# F4AIR_-.net
KiCad netlist of a schematic drawn in Altium Designer
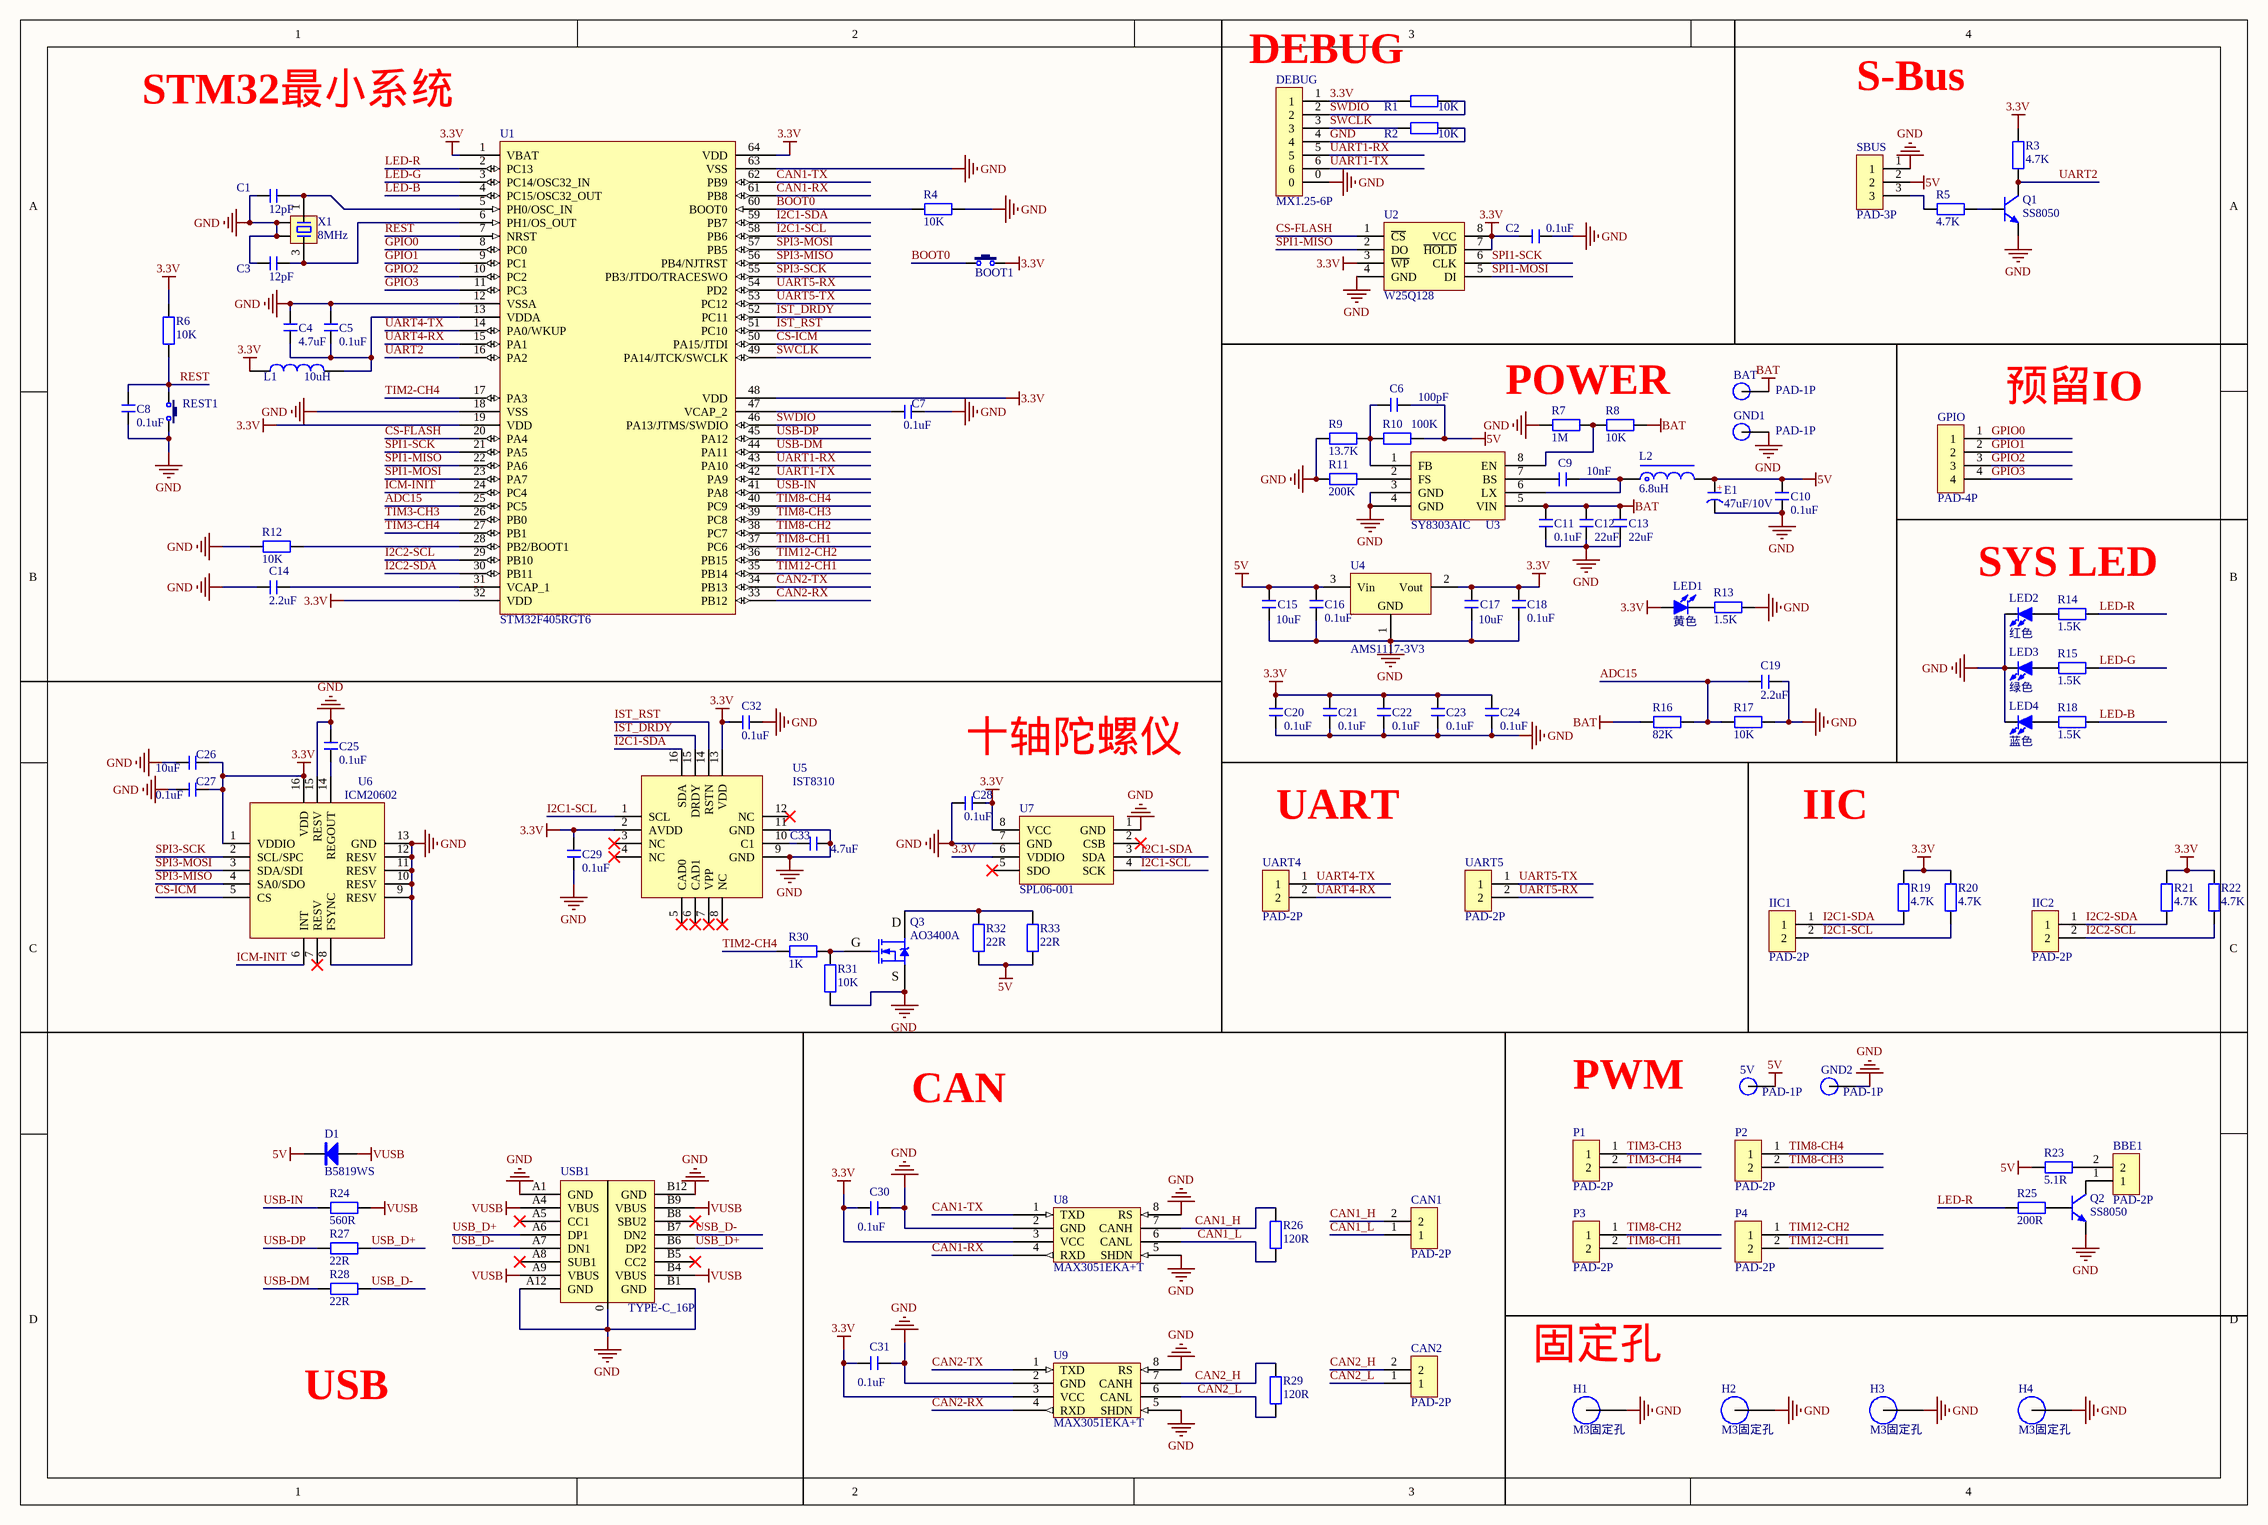
[diagram p0: F4AIR - 副本.SchDoc]

(export (version "E")
  (design (tool "Eeschema 10.0.6"))
  (components
    (comp (ref "5V") (value "PAD-1P") (footprint "PAD-4x2mm") (libsource (lib "F4AIR") (part "PAD-1P")))
    (comp (ref "BAT") (value "PAD-1P") (footprint "PAD-4x2mm") (libsource (lib "F4AIR") (part "PAD-1P")))
    (comp (ref "BBE1") (value "PAD-2P") (footprint "PAD-2.54-2P") (libsource (lib "") (part "PAD-2P_1")))
    (comp (ref "BOOT1")
      (value "3x6x5")
      (footprint "TSW SMD-3*6*5")
      (description "3x6轻触开关")
      (fields (field (name "版权归属") "源创客"))
      (libsource (lib "Schlib1") (part "TSW 3x6"))
    )
    (comp (ref "C1")
      (value "12pF")
      (footprint "C 0603_M")
      (description "无极性贴片电容")
      (fields (field (name "版权归属") "源创客"))
      (libsource (lib "Schlib1") (part "C"))
    )
    (comp (ref "C2")
      (value "0.1uF")
      (footprint "C 0603_M")
      (description "无极性贴片电容")
      (fields (field (name "版权归属") "源创客"))
      (libsource (lib "Schlib") (part "C"))
    )
    (comp (ref "C3")
      (value "12pF")
      (footprint "C 0603_M")
      (description "无极性贴片电容")
      (fields (field (name "版权归属") "源创客"))
      (libsource (lib "Schlib1") (part "C"))
    )
    (comp (ref "C4")
      (value "4.7uF")
      (footprint "C 0603_M")
      (description "无极性贴片电容")
      (fields (field (name "版权归属") "源创客"))
      (libsource (lib "Schlib1") (part "C"))
    )
    (comp (ref "C5")
      (value "0.1uF")
      (footprint "C 0603_M")
      (description "无极性贴片电容")
      (fields (field (name "版权归属") "源创客"))
      (libsource (lib "Schlib1") (part "C"))
    )
    (comp (ref "C6")
      (value "100pF")
      (footprint "C 0603_M")
      (description "无极性贴片电容")
      (fields (field (name "版权归属") "源创客"))
      (libsource (lib "Schlib1") (part "C"))
    )
    (comp (ref "C7")
      (value "0.1uF")
      (footprint "C 0603_M")
      (description "无极性贴片电容")
      (fields (field (name "版权归属") "源创客"))
      (libsource (lib "Schlib1") (part "C"))
    )
    (comp (ref "C8")
      (value "0.1uF")
      (footprint "C 0603_M")
      (description "无极性贴片电容")
      (fields (field (name "版权归属") "源创客"))
      (libsource (lib "Schlib1") (part "C"))
    )
    (comp (ref "C9")
      (value "10nF")
      (footprint "C 0603_M")
      (description "无极性贴片电容")
      (fields (field (name "版权归属") "源创客"))
      (libsource (lib "Schlib1") (part "C"))
    )
    (comp (ref "C10")
      (value "0.1uF")
      (footprint "C 0603_M")
      (description "无极性贴片电容")
      (fields (field (name "版权归属") "源创客"))
      (libsource (lib "Schlib1") (part "C"))
    )
    (comp (ref "C11")
      (value "0.1uF")
      (footprint "C 0603_M")
      (description "无极性贴片电容")
      (fields (field (name "版权归属") "源创客"))
      (libsource (lib "Schlib1") (part "C"))
    )
    (comp (ref "C12")
      (value "22uF")
      (footprint "C 1210_M")
      (description "无极性贴片电容")
      (fields (field (name "版权归属") "源创客"))
      (libsource (lib "核心板v2") (part "C"))
    )
    (comp (ref "C13")
      (value "22uF")
      (footprint "C 1210_M")
      (description "无极性贴片电容")
      (fields (field (name "版权归属") "源创客"))
      (libsource (lib "核心板v2") (part "C"))
    )
    (comp (ref "C14")
      (value "2.2uF")
      (footprint "C 0603_M")
      (description "无极性贴片电容")
      (fields (field (name "版权归属") "源创客"))
      (libsource (lib "Schlib1") (part "C"))
    )
    (comp (ref "C15")
      (value "10uF")
      (footprint "C 0805_M")
      (description "无极性贴片电容")
      (fields (field (name "版权归属") "源创客"))
      (libsource (lib "altium-import") (part "root_1_C_"))
    )
    (comp (ref "C16")
      (value "0.1uF")
      (footprint "C 0603_M")
      (description "无极性贴片电容")
      (fields (field (name "版权归属") "源创客"))
      (libsource (lib "Schlib1") (part "C"))
    )
    (comp (ref "C17")
      (value "10uF")
      (footprint "C 0805_M")
      (description "无极性贴片电容")
      (fields (field (name "版权归属") "源创客"))
      (libsource (lib "altium-import") (part "root_1_C_"))
    )
    (comp (ref "C18")
      (value "0.1uF")
      (footprint "C 0603_M")
      (description "无极性贴片电容")
      (fields (field (name "版权归属") "源创客"))
      (libsource (lib "Schlib1") (part "C"))
    )
    (comp (ref "C19")
      (value "2.2uF")
      (footprint "C 0603_M")
      (description "无极性贴片电容")
      (fields (field (name "版权归属") "源创客"))
      (libsource (lib "Schlib") (part "C"))
    )
    (comp (ref "C20")
      (value "0.1uF")
      (footprint "C 0603_M")
      (description "无极性贴片电容")
      (fields (field (name "版权归属") "源创客"))
      (libsource (lib "Schlib1") (part "C"))
    )
    (comp (ref "C21")
      (value "0.1uF")
      (footprint "C 0603_M")
      (description "无极性贴片电容")
      (fields (field (name "版权归属") "源创客"))
      (libsource (lib "Schlib1") (part "C"))
    )
    (comp (ref "C22")
      (value "0.1uF")
      (footprint "C 0603_M")
      (description "无极性贴片电容")
      (fields (field (name "版权归属") "源创客"))
      (libsource (lib "Schlib1") (part "C"))
    )
    (comp (ref "C23")
      (value "0.1uF")
      (footprint "C 0603_M")
      (description "无极性贴片电容")
      (fields (field (name "版权归属") "源创客"))
      (libsource (lib "Schlib1") (part "C"))
    )
    (comp (ref "C24")
      (value "0.1uF")
      (footprint "C 0603_M")
      (description "无极性贴片电容")
      (fields (field (name "版权归属") "源创客"))
      (libsource (lib "Schlib1") (part "C"))
    )
    (comp (ref "C25")
      (value "0.1uF")
      (footprint "C 0603_M")
      (description "无极性贴片电容")
      (fields (field (name "版权归属") "源创客"))
      (libsource (lib "Schlib1") (part "C"))
    )
    (comp (ref "C26")
      (value "10uF")
      (footprint "C 0805_M")
      (description "无极性贴片电容")
      (fields (field (name "版权归属") "源创客"))
      (libsource (lib "Schlib1") (part "C"))
    )
    (comp (ref "C27")
      (value "0.1uF")
      (footprint "C 0603_M")
      (description "无极性贴片电容")
      (fields (field (name "版权归属") "源创客"))
      (libsource (lib "Schlib1") (part "C"))
    )
    (comp (ref "C28")
      (value "0.1uF")
      (footprint "C 0603_M")
      (description "无极性贴片电容")
      (fields (field (name "版权归属") "源创客"))
      (libsource (lib "Schlib1") (part "C"))
    )
    (comp (ref "C29")
      (value "0.1uF")
      (footprint "C 0603_M")
      (description "无极性贴片电容")
      (fields (field (name "版权归属") "源创客"))
      (libsource (lib "Schlib1") (part "C"))
    )
    (comp (ref "C30")
      (value "0.1uF")
      (footprint "C 0603_M")
      (description "无极性贴片电容")
      (fields (field (name "版权归属") "源创客"))
      (libsource (lib "Schlib1") (part "C"))
    )
    (comp (ref "C31")
      (value "0.1uF")
      (footprint "C 0603_M")
      (description "无极性贴片电容")
      (fields (field (name "版权归属") "源创客"))
      (libsource (lib "Schlib1") (part "C"))
    )
    (comp (ref "C32")
      (value "0.1uF")
      (footprint "C 0603_M")
      (description "无极性贴片电容")
      (fields (field (name "版权归属") "源创客"))
      (libsource (lib "Schlib1") (part "C"))
    )
    (comp (ref "C33")
      (value "4.7uF")
      (footprint "C 0603_M")
      (description "无极性贴片电容")
      (fields (field (name "版权归属") "源创客"))
      (libsource (lib "Schlib1") (part "C"))
    )
    (comp (ref "CAN1") (value "PAD-2P") (footprint "PAD-2.54-2P") (libsource (lib "") (part "PAD-2P_1")))
    (comp (ref "CAN2") (value "PAD-2P") (footprint "PAD-2.54-2P") (libsource (lib "") (part "PAD-2P_1")))
    (comp (ref "D1")
      (value "B5819WS")
      (footprint "SOD-323")
      (description "肖特基二极管")
      (fields (field (name "版权归属") "源创客"))
      (libsource (lib "Schlib") (part "SS54"))
    )
    (comp (ref "DEBUG")
      (value "MX1.25-6P")
      (footprint "MX1.25-6P-WS")
      (libsource (lib "F4AIR") (part "MX1.25-6P"))
    )
    (comp (ref "E1")
      (value "47uF/10V")
      (footprint "CD A(3216)")
      (description "贴片钽电容")
      (fields (field (name "版权归属") "源创客"))
      (libsource (lib "核心板v2") (part "C-CD"))
    )
    (comp (ref "GND1") (value "PAD-1P") (footprint "PAD-4x2mm") (libsource (lib "F4AIR") (part "PAD-1P")))
    (comp (ref "GND2") (value "PAD-1P") (footprint "PAD-4x2mm") (libsource (lib "F4AIR") (part "PAD-1P")))
    (comp (ref "GPIO") (value "PAD-4P") (footprint "PAD-1.25-4P") (libsource (lib "F4AIR") (part "PAD-4P")))
    (comp (ref "H1")
      (value "M3固定孔")
      (footprint "M3")
      (description "铜柱孔")
      (fields (field (name "版权归属") "源创客"))
      (libsource (lib "F4AIR") (part "M3"))
    )
    (comp (ref "H2")
      (value "M3固定孔")
      (footprint "M3")
      (description "铜柱孔")
      (fields (field (name "版权归属") "源创客"))
      (libsource (lib "F4AIR") (part "M3"))
    )
    (comp (ref "H3")
      (value "M3固定孔")
      (footprint "M3")
      (description "铜柱孔")
      (fields (field (name "版权归属") "源创客"))
      (libsource (lib "F4AIR") (part "M3"))
    )
    (comp (ref "H4")
      (value "M3固定孔")
      (footprint "M3")
      (description "铜柱孔")
      (fields (field (name "版权归属") "源创客"))
      (libsource (lib "F4AIR") (part "M3"))
    )
    (comp (ref "IIC1") (value "PAD-2P") (footprint "PAD-2.54-2P") (libsource (lib "F4AIR") (part "PAD-2P")))
    (comp (ref "IIC2") (value "PAD-2P") (footprint "PAD-2.54-2P") (libsource (lib "F4AIR") (part "PAD-2P")))
    (comp (ref "L1")
      (value "10uH")
      (footprint "L 0603")
      (description "小功率贴片电感")
      (fields (field (name "版权归属") "源创客"))
      (libsource (lib "Schlib1") (part "L"))
    )
    (comp (ref "L2")
      (value "6.8uH")
      (footprint "L-SMD-0630")
      (description "贴片功率电感")
      (fields (field (name "版权归属") "源创客"))
      (libsource (lib "核心板v2") (part "L-CD"))
    )
    (comp (ref "LED1")
      (value "黄色")
      (footprint "LED 0603Y")
      (description "贴片LED")
      (fields (field (name "版权归属") "源创客"))
      (libsource (lib "核心板v2") (part "LED-SMD"))
    )
    (comp (ref "LED2")
      (value "红色")
      (footprint "LED 0603R")
      (description "贴片LED")
      (fields (field (name "版权归属") "源创客"))
      (libsource (lib "核心板v2") (part "LED-SMD"))
    )
    (comp (ref "LED3")
      (value "绿色")
      (footprint "LED 0603G")
      (description "贴片LED")
      (fields (field (name "版权归属") "源创客"))
      (libsource (lib "核心板v2") (part "LED-SMD"))
    )
    (comp (ref "LED4")
      (value "蓝色")
      (footprint "LED 0603B")
      (description "贴片LED")
      (fields (field (name "版权归属") "源创客"))
      (libsource (lib "核心板v2") (part "LED-SMD"))
    )
    (comp (ref "P1") (value "PAD-2P") (footprint "PAD-2.54-2P") (libsource (lib "F4AIR") (part "PAD-2P")))
    (comp (ref "P2") (value "PAD-2P") (footprint "PAD-2.54-2P") (libsource (lib "F4AIR") (part "PAD-2P")))
    (comp (ref "P3") (value "PAD-2P") (footprint "PAD-2.54-2P") (libsource (lib "F4AIR") (part "PAD-2P")))
    (comp (ref "P4") (value "PAD-2P") (footprint "PAD-2.54-2P") (libsource (lib "F4AIR") (part "PAD-2P")))
    (comp (ref "Q1")
      (value "SS8050")
      (footprint "SOT23-3M")
      (description "高频放大-NPN型")
      (libsource (lib "Schlib1") (part "8050-SMD"))
    )
    (comp (ref "Q2")
      (value "SS8050")
      (footprint "SOT23-3M")
      (description "高频放大-NPN型")
      (libsource (lib "核心板v2") (part "8050-SMD"))
    )
    (comp (ref "Q3") (value "AO3400A") (footprint "SOT23-3M") (libsource (lib "F4AIR") (part "AO3400A")))
    (comp (ref "R1")
      (value "10K")
      (footprint "R 0603_M")
      (description "贴片电阻")
      (fields (field (name "版权归属") "源创客"))
      (libsource (lib "Schlib1") (part "R"))
    )
    (comp (ref "R2")
      (value "10K")
      (footprint "R 0603_M")
      (description "贴片电阻")
      (fields (field (name "版权归属") "源创客"))
      (libsource (lib "Schlib1") (part "R"))
    )
    (comp (ref "R3")
      (value "4.7K")
      (footprint "R 0603_M")
      (description "贴片电阻")
      (fields (field (name "版权归属") "源创客"))
      (libsource (lib "Schlib1") (part "R"))
    )
    (comp (ref "R4")
      (value "10K")
      (footprint "R 0603_M")
      (description "贴片电阻")
      (fields (field (name "版权归属") "源创客"))
      (libsource (lib "Schlib1") (part "R"))
    )
    (comp (ref "R5")
      (value "4.7K")
      (footprint "R 0603_M")
      (description "贴片电阻")
      (fields (field (name "版权归属") "源创客"))
      (libsource (lib "Schlib1") (part "R"))
    )
    (comp (ref "R6")
      (value "10K")
      (footprint "R 0603_M")
      (description "贴片电阻")
      (fields (field (name "版权归属") "源创客"))
      (libsource (lib "Schlib1") (part "R"))
    )
    (comp (ref "R7")
      (value "1M")
      (footprint "R 0603_M")
      (description "贴片电阻")
      (fields (field (name "版权归属") "源创客"))
      (libsource (lib "altium-import") (part "root_2_R_"))
    )
    (comp (ref "R8")
      (value "10K")
      (footprint "R 0603_M")
      (description "贴片电阻")
      (fields (field (name "版权归属") "源创客"))
      (libsource (lib "altium-import") (part "root_2_R_"))
    )
    (comp (ref "R9")
      (value "13.7K")
      (footprint "R 0603_M")
      (description "贴片电阻")
      (fields (field (name "版权归属") "源创客"))
      (libsource (lib "altium-import") (part "root_2_R_"))
    )
    (comp (ref "R10")
      (value "100K")
      (footprint "R 0603_M")
      (description "贴片电阻")
      (fields (field (name "版权归属") "源创客"))
      (libsource (lib "altium-import") (part "root_2_R_"))
    )
    (comp (ref "R11")
      (value "200K")
      (footprint "R 0603_M")
      (description "贴片电阻")
      (fields (field (name "版权归属") "源创客"))
      (libsource (lib "altium-import") (part "root_2_R_"))
    )
    (comp (ref "R12")
      (value "10K")
      (footprint "R 0603_M")
      (description "贴片电阻")
      (fields (field (name "版权归属") "源创客"))
      (libsource (lib "Schlib1") (part "R"))
    )
    (comp (ref "R13")
      (value "1.5K")
      (footprint "R 0603_M")
      (description "贴片电阻")
      (fields (field (name "版权归属") "源创客"))
      (libsource (lib "核心板v2") (part "R"))
    )
    (comp (ref "R14")
      (value "1.5K")
      (footprint "R 0603_M")
      (description "贴片电阻")
      (fields (field (name "版权归属") "源创客"))
      (libsource (lib "核心板v2") (part "R"))
    )
    (comp (ref "R15")
      (value "1.5K")
      (footprint "R 0603_M")
      (description "贴片电阻")
      (fields (field (name "版权归属") "源创客"))
      (libsource (lib "核心板v2") (part "R"))
    )
    (comp (ref "R16")
      (value "82K")
      (footprint "R 0603_M")
      (description "贴片电阻")
      (fields (field (name "版权归属") "源创客"))
      (libsource (lib "Schlib") (part "R"))
    )
    (comp (ref "R17")
      (value "10K")
      (footprint "R 0603_M")
      (description "贴片电阻")
      (fields (field (name "版权归属") "源创客"))
      (libsource (lib "Schlib") (part "R"))
    )
    (comp (ref "R18")
      (value "1.5K")
      (footprint "R 0603_M")
      (description "贴片电阻")
      (fields (field (name "版权归属") "源创客"))
      (libsource (lib "核心板v2") (part "R"))
    )
    (comp (ref "R19")
      (value "4.7K")
      (footprint "R 0603_M")
      (description "贴片电阻")
      (fields (field (name "版权归属") "源创客"))
      (libsource (lib "altium-import") (part "root_3_R_"))
    )
    (comp (ref "R20")
      (value "4.7K")
      (footprint "R 0603_M")
      (description "贴片电阻")
      (fields (field (name "版权归属") "源创客"))
      (libsource (lib "altium-import") (part "root_1_R_"))
    )
    (comp (ref "R21")
      (value "4.7K")
      (footprint "R 0603_M")
      (description "贴片电阻")
      (fields (field (name "版权归属") "源创客"))
      (libsource (lib "altium-import") (part "root_3_R_"))
    )
    (comp (ref "R22")
      (value "4.7K")
      (footprint "R 0603_M")
      (description "贴片电阻")
      (fields (field (name "版权归属") "源创客"))
      (libsource (lib "altium-import") (part "root_1_R_"))
    )
    (comp (ref "R23")
      (value "5.1R")
      (footprint "R 0603_M")
      (description "贴片电阻")
      (fields (field (name "版权归属") "源创客"))
      (libsource (lib "核心板v2") (part "R"))
    )
    (comp (ref "R24")
      (value "560R")
      (footprint "R 0603_M")
      (description "贴片电阻")
      (fields (field (name "版权归属") "源创客"))
      (libsource (lib "Schlib1") (part "R"))
    )
    (comp (ref "R25")
      (value "200R")
      (footprint "R 0603_M")
      (description "贴片电阻")
      (fields (field (name "版权归属") "源创客"))
      (libsource (lib "核心板v2") (part "R"))
    )
    (comp (ref "R26")
      (value "120R")
      (footprint "R 0603_M")
      (description "贴片电阻")
      (fields (field (name "版权归属") "源创客"))
      (libsource (lib "altium-import") (part "root_1_R_"))
    )
    (comp (ref "R27")
      (value "22R")
      (footprint "R 0603_M")
      (description "贴片电阻")
      (fields (field (name "版权归属") "源创客"))
      (libsource (lib "Schlib") (part "R"))
    )
    (comp (ref "R28")
      (value "22R")
      (footprint "R 0603_M")
      (description "贴片电阻")
      (fields (field (name "版权归属") "源创客"))
      (libsource (lib "Schlib") (part "R"))
    )
    (comp (ref "R29")
      (value "120R")
      (footprint "R 0603_M")
      (description "贴片电阻")
      (fields (field (name "版权归属") "源创客"))
      (libsource (lib "altium-import") (part "root_1_R_"))
    )
    (comp (ref "R30")
      (value "1K")
      (footprint "R 0603_M")
      (description "贴片电阻")
      (fields (field (name "版权归属") "源创客"))
      (libsource (lib "F4AIR") (part "R"))
    )
    (comp (ref "R31")
      (value "10K")
      (footprint "R 0603_M")
      (description "贴片电阻")
      (fields (field (name "版权归属") "源创客"))
      (libsource (lib "F4AIR") (part "R"))
    )
    (comp (ref "R32")
      (value "22R")
      (footprint "R 0603_M")
      (description "贴片电阻")
      (fields (field (name "版权归属") "源创客"))
      (libsource (lib "F4AIR") (part "R"))
    )
    (comp (ref "R33")
      (value "22R")
      (footprint "R 0603_M")
      (description "贴片电阻")
      (fields (field (name "版权归属") "源创客"))
      (libsource (lib "F4AIR") (part "R"))
    )
    (comp (ref "REST1")
      (value "3x6x5")
      (footprint "TSW SMD-3*6*5")
      (description "3x6轻触开关")
      (fields (field (name "版权归属") "源创客"))
      (libsource (lib "") (part "TSW 3x6_1"))
    )
    (comp (ref "SBUS") (value "PAD-3P") (footprint "PAD-2.54-3P") (libsource (lib "F4AIR") (part "PAD-3P")))
    (comp (ref "U1")
      (value "STM32F405RGT6")
      (footprint "LQFP64")
      (libsource (lib "Schlib") (part "STM32F405RGT6"))
    )
    (comp (ref "U2")
      (value "W25Q128")
      (footprint "SOP8_M - 208mil")
      (libsource (lib "Schlib") (part "W25Q128"))
    )
    (comp (ref "U3")
      (value "SY8303AIC")
      (footprint "SOT23-8")
      (description "DCDC降压芯片")
      (libsource (lib "核心板v2") (part "SY8303AIC"))
    )
    (comp (ref "U4")
      (value "AMS1117-3V3")
      (footprint "SOT-89")
      (description "三端稳压芯片")
      (fields (field (name "版权归属") "源创客"))
      (libsource (lib "F4AIR") (part "AMS1117"))
    )
    (comp (ref "U5")
      (value "IST8310")
      (footprint "LGA16 3x3")
      (description "三轴电子罗盘")
      (libsource (lib "F4AIR") (part "IST8310"))
    )
    (comp (ref "U6") (value "ICM20602") (footprint "LGA16") (libsource (lib "Schlib1") (part "ICM20602")))
    (comp (ref "U7") (value "SPL06-001") (footprint "LGA08") (libsource (lib "Schlib1") (part "SPL06")))
    (comp (ref "U8")
      (value "MAX3051EKA+T")
      (footprint "SOT23-8")
      (description "CAN芯片")
      (libsource (lib "核心板v2") (part "MAX3051EKA+T"))
    )
    (comp (ref "U9")
      (value "MAX3051EKA+T")
      (footprint "SOT23-8")
      (description "CAN芯片")
      (libsource (lib "核心板v2") (part "MAX3051EKA+T"))
    )
    (comp (ref "UART4") (value "PAD-2P") (footprint "PAD-2.54-2P") (libsource (lib "F4AIR") (part "PAD-2P")))
    (comp (ref "UART5") (value "PAD-2P") (footprint "PAD-2.54-2P") (libsource (lib "F4AIR") (part "PAD-2P")))
    (comp (ref "USB1")
      (value "TYPE-C_16P")
      (footprint "Type-C_16p")
      (libsource (lib "Schlib") (part "TYPE-C_16P"))
    )
    (comp (ref "X1")
      (value "8MHz")
      (footprint "OSC 3225-4P")
      (description "4脚无源晶振")
      (fields (field (name "版权归属") "源创客"))
      (libsource (lib "Schlib1") (part "XTAL-4P"))
    )
  )
  (nets
    (net (code "1") (name "/ADC15") (class "Default")
      (node (ref "C19") (pin "1") (pinfunction "1_1") (pintype "passive"))
      (node (ref "R16") (pin "2") (pinfunction "2_2") (pintype "passive"))
      (node (ref "R17") (pin "1") (pinfunction "1_1") (pintype "passive"))
      (node (ref "U1") (pin "25") (pinfunction "PC5_25") (pintype "bidirectional"))
    )
    (net (code "2") (name "/BOOT0") (class "Default")
      (node (ref "BOOT1") (pin "1") (pinfunction "1_1") (pintype "passive"))
      (node (ref "R4") (pin "1") (pinfunction "1_1") (pintype "passive"))
      (node (ref "U1") (pin "60") (pinfunction "BOOT0_60") (pintype "input"))
    )
    (net (code "3") (name "/CAN1-RX") (class "Default")
      (node (ref "U1") (pin "61") (pinfunction "PB8_61") (pintype "bidirectional"))
      (node (ref "U8") (pin "4") (pinfunction "RXD_4") (pintype "output"))
    )
    (net (code "4") (name "/CAN1-TX") (class "Default")
      (node (ref "U1") (pin "62") (pinfunction "PB9_62") (pintype "bidirectional"))
      (node (ref "U8") (pin "1") (pinfunction "TXD_1") (pintype "input"))
    )
    (net (code "5") (name "/CAN1_H") (class "Default")
      (node (ref "CAN1") (pin "2") (pinfunction "2_2") (pintype "passive"))
      (node (ref "R26") (pin "2") (pinfunction "2_2") (pintype "passive"))
      (node (ref "U8") (pin "7") (pinfunction "CANH_7") (pintype "passive"))
    )
    (net (code "6") (name "/CAN1_L") (class "Default")
      (node (ref "CAN1") (pin "1") (pinfunction "1_1") (pintype "passive"))
      (node (ref "R26") (pin "1") (pinfunction "1_1") (pintype "passive"))
      (node (ref "U8") (pin "6") (pinfunction "CANL_6") (pintype "passive"))
    )
    (net (code "7") (name "/CAN2-RX") (class "Default")
      (node (ref "U1") (pin "33") (pinfunction "PB12_33") (pintype "bidirectional"))
      (node (ref "U9") (pin "4") (pinfunction "RXD_4") (pintype "output"))
    )
    (net (code "8") (name "/CAN2-TX") (class "Default")
      (node (ref "U1") (pin "34") (pinfunction "PB13_34") (pintype "bidirectional"))
      (node (ref "U9") (pin "1") (pinfunction "TXD_1") (pintype "input"))
    )
    (net (code "9") (name "/CAN2_H") (class "Default")
      (node (ref "CAN2") (pin "2") (pinfunction "2_2") (pintype "passive"))
      (node (ref "R29") (pin "2") (pinfunction "2_2") (pintype "passive"))
      (node (ref "U9") (pin "7") (pinfunction "CANH_7") (pintype "passive"))
    )
    (net (code "10") (name "/CAN2_L") (class "Default")
      (node (ref "CAN2") (pin "1") (pinfunction "1_1") (pintype "passive"))
      (node (ref "R29") (pin "1") (pinfunction "1_1") (pintype "passive"))
      (node (ref "U9") (pin "6") (pinfunction "CANL_6") (pintype "passive"))
    )
    (net (code "11") (name "/CS-FLASH") (class "Default")
      (node (ref "U1") (pin "20") (pinfunction "PA4_20") (pintype "bidirectional"))
      (node (ref "U2") (pin "1") (pinfunction "~{CS}_1") (pintype "passive"))
    )
    (net (code "12") (name "/CS-ICM") (class "Default")
      (node (ref "U1") (pin "50") (pinfunction "PA15/JTDI_50") (pintype "bidirectional"))
      (node (ref "U6") (pin "5") (pinfunction "CS_5") (pintype "passive"))
    )
    (net (code "13") (name "/GPIO0") (class "Default")
      (node (ref "GPIO") (pin "1") (pinfunction "1_1") (pintype "passive"))
      (node (ref "U1") (pin "8") (pinfunction "PC0_8") (pintype "bidirectional"))
    )
    (net (code "14") (name "/GPIO1") (class "Default")
      (node (ref "GPIO") (pin "2") (pinfunction "2_2") (pintype "passive"))
      (node (ref "U1") (pin "9") (pinfunction "PC1_9") (pintype "bidirectional"))
    )
    (net (code "15") (name "/GPIO2") (class "Default")
      (node (ref "GPIO") (pin "3") (pinfunction "3_3") (pintype "passive"))
      (node (ref "U1") (pin "10") (pinfunction "PC2_10") (pintype "bidirectional"))
    )
    (net (code "16") (name "/GPIO3") (class "Default")
      (node (ref "GPIO") (pin "4") (pinfunction "4_4") (pintype "passive"))
      (node (ref "U1") (pin "11") (pinfunction "PC3_11") (pintype "bidirectional"))
    )
    (net (code "17") (name "/I2C1-SCL") (class "Default")
      (node (ref "IIC1") (pin "2") (pinfunction "2_2") (pintype "passive"))
      (node (ref "R20") (pin "1") (pinfunction "1_1") (pintype "passive"))
      (node (ref "U1") (pin "58") (pinfunction "PB6_58") (pintype "bidirectional"))
      (node (ref "U5") (pin "1") (pinfunction "SCL_1") (pintype "passive"))
      (node (ref "U7") (pin "4") (pinfunction "SCK_4") (pintype "passive"))
    )
    (net (code "18") (name "/I2C1-SDA") (class "Default")
      (node (ref "IIC1") (pin "1") (pinfunction "1_1") (pintype "passive"))
      (node (ref "R19") (pin "2") (pinfunction "2_2") (pintype "passive"))
      (node (ref "U1") (pin "59") (pinfunction "PB7_59") (pintype "bidirectional"))
      (node (ref "U5") (pin "16") (pinfunction "SDA_16") (pintype "passive"))
      (node (ref "U7") (pin "3") (pinfunction "SDA_3") (pintype "passive"))
    )
    (net (code "19") (name "/I2C2-SCL") (class "Default")
      (node (ref "IIC2") (pin "2") (pinfunction "2_2") (pintype "passive"))
      (node (ref "R22") (pin "1") (pinfunction "1_1") (pintype "passive"))
      (node (ref "U1") (pin "29") (pinfunction "PB10_29") (pintype "bidirectional"))
    )
    (net (code "20") (name "/I2C2-SDA") (class "Default")
      (node (ref "IIC2") (pin "1") (pinfunction "1_1") (pintype "passive"))
      (node (ref "R21") (pin "2") (pinfunction "2_2") (pintype "passive"))
      (node (ref "U1") (pin "30") (pinfunction "PB11_30") (pintype "bidirectional"))
    )
    (net (code "21") (name "/ICM-INIT") (class "Default")
      (node (ref "U1") (pin "24") (pinfunction "PC4_24") (pintype "bidirectional"))
      (node (ref "U6") (pin "6") (pinfunction "INT_6") (pintype "passive"))
    )
    (net (code "22") (name "/IST_DRDY") (class "Default")
      (node (ref "U1") (pin "52") (pinfunction "PC11_52") (pintype "bidirectional"))
      (node (ref "U5") (pin "15") (pinfunction "DRDY_15") (pintype "passive"))
    )
    (net (code "23") (name "/IST_RST") (class "Default")
      (node (ref "U1") (pin "51") (pinfunction "PC10_51") (pintype "bidirectional"))
      (node (ref "U5") (pin "14") (pinfunction "RSTN_14") (pintype "passive"))
    )
    (net (code "24") (name "/LED-B") (class "Default")
      (node (ref "R18") (pin "2") (pinfunction "2_2") (pintype "passive"))
      (node (ref "U1") (pin "4") (pinfunction "PC15/OSC32_OUT_4") (pintype "bidirectional"))
    )
    (net (code "25") (name "/LED-G") (class "Default")
      (node (ref "R15") (pin "2") (pinfunction "2_2") (pintype "passive"))
      (node (ref "U1") (pin "3") (pinfunction "PC14/OSC32_IN_3") (pintype "bidirectional"))
    )
    (net (code "26") (name "/LED-R") (class "Default")
      (node (ref "R14") (pin "2") (pinfunction "2_2") (pintype "passive"))
      (node (ref "R25") (pin "1") (pinfunction "1_1") (pintype "passive"))
      (node (ref "U1") (pin "2") (pinfunction "PC13_2") (pintype "bidirectional"))
    )
    (net (code "27") (name "/REST") (class "Default")
      (node (ref "C8") (pin "2") (pinfunction "2_2") (pintype "passive"))
      (node (ref "R6") (pin "1") (pinfunction "1_1") (pintype "passive"))
      (node (ref "REST1") (pin "1") (pinfunction "1_1") (pintype "passive"))
      (node (ref "U1") (pin "7") (pinfunction "NRST_7") (pintype "input"))
    )
    (net (code "28") (name "/SPI1-MISO") (class "Default")
      (node (ref "U1") (pin "22") (pinfunction "PA6_22") (pintype "bidirectional"))
      (node (ref "U2") (pin "2") (pinfunction "DO_2") (pintype "passive"))
    )
    (net (code "29") (name "/SPI1-MOSI") (class "Default")
      (node (ref "U1") (pin "23") (pinfunction "PA7_23") (pintype "bidirectional"))
      (node (ref "U2") (pin "5") (pinfunction "DI_5") (pintype "passive"))
    )
    (net (code "30") (name "/SPI1-SCK") (class "Default")
      (node (ref "U1") (pin "21") (pinfunction "PA5_21") (pintype "bidirectional"))
      (node (ref "U2") (pin "6") (pinfunction "CLK_6") (pintype "passive"))
    )
    (net (code "31") (name "/SPI3-MISO") (class "Default")
      (node (ref "U1") (pin "56") (pinfunction "PB4/NJTRST_56") (pintype "bidirectional"))
      (node (ref "U6") (pin "4") (pinfunction "SA0/SDO_4") (pintype "passive"))
    )
    (net (code "32") (name "/SPI3-MOSI") (class "Default")
      (node (ref "U1") (pin "57") (pinfunction "PB5_57") (pintype "bidirectional"))
      (node (ref "U6") (pin "3") (pinfunction "SDA/SDI_3") (pintype "passive"))
    )
    (net (code "33") (name "/SPI3-SCK") (class "Default")
      (node (ref "U1") (pin "55") (pinfunction "PB3/JTDO/TRACESWO_55") (pintype "bidirectional"))
      (node (ref "U6") (pin "2") (pinfunction "SCL/SPC_2") (pintype "passive"))
    )
    (net (code "34") (name "/SWCLK") (class "Default")
      (node (ref "DEBUG") (pin "3") (pinfunction "3_3") (pintype "passive"))
      (node (ref "R2") (pin "1") (pinfunction "1_1") (pintype "passive"))
      (node (ref "U1") (pin "49") (pinfunction "PA14/JTCK/SWCLK_49") (pintype "bidirectional"))
    )
    (net (code "35") (name "/SWDIO") (class "Default")
      (node (ref "DEBUG") (pin "2") (pinfunction "2_2") (pintype "passive"))
      (node (ref "R1") (pin "2") (pinfunction "2_2") (pintype "passive"))
      (node (ref "U1") (pin "46") (pinfunction "PA13/JTMS/SWDIO_46") (pintype "bidirectional"))
    )
    (net (code "36") (name "/TIM2-CH4") (class "Default")
      (node (ref "R30") (pin "1") (pinfunction "1_1") (pintype "passive"))
      (node (ref "U1") (pin "17") (pinfunction "PA3_17") (pintype "bidirectional"))
    )
    (net (code "37") (name "/TIM3-CH3") (class "Default")
      (node (ref "P1") (pin "1") (pinfunction "1_1") (pintype "passive"))
      (node (ref "U1") (pin "26") (pinfunction "PB0_26") (pintype "bidirectional"))
    )
    (net (code "38") (name "/TIM3-CH4") (class "Default")
      (node (ref "P1") (pin "2") (pinfunction "2_2") (pintype "passive"))
      (node (ref "U1") (pin "27") (pinfunction "PB1_27") (pintype "bidirectional"))
    )
    (net (code "39") (name "/TIM8-CH1") (class "Default")
      (node (ref "P3") (pin "2") (pinfunction "2_2") (pintype "passive"))
      (node (ref "U1") (pin "37") (pinfunction "PC6_37") (pintype "bidirectional"))
    )
    (net (code "40") (name "/TIM8-CH2") (class "Default")
      (node (ref "P3") (pin "1") (pinfunction "1_1") (pintype "passive"))
      (node (ref "U1") (pin "38") (pinfunction "PC7_38") (pintype "bidirectional"))
    )
    (net (code "41") (name "/TIM8-CH3") (class "Default")
      (node (ref "P2") (pin "2") (pinfunction "2_2") (pintype "passive"))
      (node (ref "U1") (pin "39") (pinfunction "PC8_39") (pintype "bidirectional"))
    )
    (net (code "42") (name "/TIM8-CH4") (class "Default")
      (node (ref "P2") (pin "1") (pinfunction "1_1") (pintype "passive"))
      (node (ref "U1") (pin "40") (pinfunction "PC9_40") (pintype "bidirectional"))
    )
    (net (code "43") (name "/TIM12-CH1") (class "Default")
      (node (ref "P4") (pin "2") (pinfunction "2_2") (pintype "passive"))
      (node (ref "U1") (pin "35") (pinfunction "PB14_35") (pintype "bidirectional"))
    )
    (net (code "44") (name "/TIM12-CH2") (class "Default")
      (node (ref "P4") (pin "1") (pinfunction "1_1") (pintype "passive"))
      (node (ref "U1") (pin "36") (pinfunction "PB15_36") (pintype "bidirectional"))
    )
    (net (code "45") (name "/UART1-RX") (class "Default")
      (node (ref "DEBUG") (pin "5") (pinfunction "5_5") (pintype "passive"))
      (node (ref "U1") (pin "43") (pinfunction "PA10_43") (pintype "bidirectional"))
    )
    (net (code "46") (name "/UART1-TX") (class "Default")
      (node (ref "DEBUG") (pin "6") (pinfunction "6_6") (pintype "passive"))
      (node (ref "U1") (pin "42") (pinfunction "PA9_42") (pintype "bidirectional"))
    )
    (net (code "47") (name "/UART2") (class "Default")
      (node (ref "Q1") (pin "3") (pinfunction "C_3") (pintype "passive"))
      (node (ref "R3") (pin "1") (pinfunction "1_1") (pintype "passive"))
      (node (ref "U1") (pin "16") (pinfunction "PA2_16") (pintype "bidirectional"))
    )
    (net (code "48") (name "/UART4-RX") (class "Default")
      (node (ref "U1") (pin "15") (pinfunction "PA1_15") (pintype "bidirectional"))
      (node (ref "UART4") (pin "2") (pinfunction "2_2") (pintype "passive"))
    )
    (net (code "49") (name "/UART4-TX") (class "Default")
      (node (ref "U1") (pin "14") (pinfunction "PA0/WKUP_14") (pintype "bidirectional"))
      (node (ref "UART4") (pin "1") (pinfunction "1_1") (pintype "passive"))
    )
    (net (code "50") (name "/UART5-RX") (class "Default")
      (node (ref "U1") (pin "54") (pinfunction "PD2_54") (pintype "bidirectional"))
      (node (ref "UART5") (pin "2") (pinfunction "2_2") (pintype "passive"))
    )
    (net (code "51") (name "/UART5-TX") (class "Default")
      (node (ref "U1") (pin "53") (pinfunction "PC12_53") (pintype "bidirectional"))
      (node (ref "UART5") (pin "1") (pinfunction "1_1") (pintype "passive"))
    )
    (net (code "52") (name "/USB-DM") (class "Default")
      (node (ref "R28") (pin "1") (pinfunction "1_1") (pintype "passive"))
      (node (ref "U1") (pin "44") (pinfunction "PA11_44") (pintype "bidirectional"))
    )
    (net (code "53") (name "/USB-DP") (class "Default")
      (node (ref "R27") (pin "1") (pinfunction "1_1") (pintype "passive"))
      (node (ref "U1") (pin "45") (pinfunction "PA12_45") (pintype "bidirectional"))
    )
    (net (code "54") (name "/USB-IN") (class "Default")
      (node (ref "R24") (pin "1") (pinfunction "1_1") (pintype "passive"))
      (node (ref "U1") (pin "41") (pinfunction "PA8_41") (pintype "bidirectional"))
    )
    (net (code "55") (name "/USB_D+") (class "Default")
      (node (ref "R27") (pin "2") (pinfunction "2_2") (pintype "passive"))
      (node (ref "USB1") (pin "A6") (pinfunction "DP1_A6") (pintype "passive"))
      (node (ref "USB1") (pin "B6") (pinfunction "DP2_B6") (pintype "passive"))
    )
    (net (code "56") (name "/USB_D-") (class "Default")
      (node (ref "R28") (pin "2") (pinfunction "2_2") (pintype "passive"))
      (node (ref "USB1") (pin "A7") (pinfunction "DN1_A7") (pintype "passive"))
      (node (ref "USB1") (pin "B7") (pinfunction "DN2_B7") (pintype "passive"))
    )
    (net (code "57") (name "3.3V") (class "Default")
      (node (ref "BOOT1") (pin "2") (pinfunction "2_2") (pintype "passive"))
      (node (ref "C17") (pin "2") (pinfunction "2_2") (pintype "passive"))
      (node (ref "C18") (pin "1") (pinfunction "1_1") (pintype "passive"))
      (node (ref "C2") (pin "1") (pinfunction "1_1") (pintype "passive"))
      (node (ref "C20") (pin "1") (pinfunction "1_1") (pintype "passive"))
      (node (ref "C21") (pin "1") (pinfunction "1_1") (pintype "passive"))
      (node (ref "C22") (pin "1") (pinfunction "1_1") (pintype "passive"))
      (node (ref "C23") (pin "1") (pinfunction "1_1") (pintype "passive"))
      (node (ref "C24") (pin "1") (pinfunction "1_1") (pintype "passive"))
      (node (ref "C26") (pin "2") (pinfunction "2_2") (pintype "passive"))
      (node (ref "C27") (pin "2") (pinfunction "2_2") (pintype "passive"))
      (node (ref "C28") (pin "2") (pinfunction "2_2") (pintype "passive"))
      (node (ref "C29") (pin "2") (pinfunction "2_2") (pintype "passive"))
      (node (ref "C30") (pin "2") (pinfunction "2_2") (pintype "passive"))
      (node (ref "C31") (pin "2") (pinfunction "2_2") (pintype "passive"))
      (node (ref "C32") (pin "2") (pinfunction "2_2") (pintype "passive"))
      (node (ref "DEBUG") (pin "1") (pinfunction "1_1") (pintype "passive"))
      (node (ref "L1") (pin "1") (pinfunction "1_1") (pintype "passive"))
      (node (ref "LED1") (pin "1") (pinfunction "A_1") (pintype "passive"))
      (node (ref "R1") (pin "1") (pinfunction "1_1") (pintype "passive"))
      (node (ref "R19") (pin "1") (pinfunction "1_1") (pintype "passive"))
      (node (ref "R20") (pin "2") (pinfunction "2_2") (pintype "passive"))
      (node (ref "R21") (pin "1") (pinfunction "1_1") (pintype "passive"))
      (node (ref "R22") (pin "2") (pinfunction "2_2") (pintype "passive"))
      (node (ref "R3") (pin "2") (pinfunction "2_2") (pintype "passive"))
      (node (ref "R6") (pin "2") (pinfunction "2_2") (pintype "passive"))
      (node (ref "U1") (pin "1") (pinfunction "VBAT_1") (pintype "power_in"))
      (node (ref "U1") (pin "19") (pinfunction "VDD_19") (pintype "power_in"))
      (node (ref "U1") (pin "32") (pinfunction "VDD_32") (pintype "power_in"))
      (node (ref "U1") (pin "48") (pinfunction "VDD_48") (pintype "power_in"))
      (node (ref "U1") (pin "64") (pinfunction "VDD_64") (pintype "power_in"))
      (node (ref "U2") (pin "3") (pinfunction "~{WP}_3") (pintype "passive"))
      (node (ref "U2") (pin "7") (pinfunction "~{HOLD}_7") (pintype "passive"))
      (node (ref "U2") (pin "8") (pinfunction "VCC_8") (pintype "passive"))
      (node (ref "U4") (pin "2") (pinfunction "Vout_2") (pintype "passive"))
      (node (ref "U5") (pin "13") (pinfunction "VDD_13") (pintype "passive"))
      (node (ref "U5") (pin "2") (pinfunction "AVDD_2") (pintype "passive"))
      (node (ref "U6") (pin "1") (pinfunction "VDDIO_1") (pintype "passive"))
      (node (ref "U6") (pin "16") (pinfunction "VDD_16") (pintype "passive"))
      (node (ref "U7") (pin "6") (pinfunction "VDDIO_6") (pintype "passive"))
      (node (ref "U7") (pin "8") (pinfunction "VCC_8") (pintype "passive"))
      (node (ref "U8") (pin "3") (pinfunction "VCC_3") (pintype "power_in"))
      (node (ref "U9") (pin "3") (pinfunction "VCC_3") (pintype "power_in"))
    )
    (net (code "58") (name "5V") (class "Default")
      (node (ref "5V") (pin "1") (pinfunction "1_1") (pintype "passive"))
      (node (ref "C10") (pin "1") (pinfunction "1_1") (pintype "passive"))
      (node (ref "C15") (pin "2") (pinfunction "2_2") (pintype "passive"))
      (node (ref "C16") (pin "1") (pinfunction "1_1") (pintype "passive"))
      (node (ref "C6") (pin "1") (pinfunction "1_1") (pintype "passive"))
      (node (ref "D1") (pin "2") (pinfunction "K_2") (pintype "passive"))
      (node (ref "E1") (pin "1") (pinfunction "A_1") (pintype "passive"))
      (node (ref "L2") (pin "2") (pinfunction "2_2") (pintype "passive"))
      (node (ref "R10") (pin "1") (pinfunction "1_1") (pintype "passive"))
      (node (ref "R23") (pin "1") (pinfunction "1_1") (pintype "passive"))
      (node (ref "R32") (pin "1") (pinfunction "1_1") (pintype "passive"))
      (node (ref "R33") (pin "1") (pinfunction "1_1") (pintype "passive"))
      (node (ref "SBUS") (pin "2") (pinfunction "2_2") (pintype "passive"))
      (node (ref "U4") (pin "3") (pinfunction "Vin_3") (pintype "passive"))
    )
    (net (code "59") (name "BAT") (class "Default")
      (node (ref "BAT") (pin "1") (pinfunction "1_1") (pintype "passive"))
      (node (ref "C11") (pin "1") (pinfunction "1_1") (pintype "passive"))
      (node (ref "C12") (pin "2") (pinfunction "2_2") (pintype "passive"))
      (node (ref "C13") (pin "2") (pinfunction "2_2") (pintype "passive"))
      (node (ref "R16") (pin "1") (pinfunction "1_1") (pintype "passive"))
      (node (ref "R8") (pin "1") (pinfunction "1_1") (pintype "passive"))
      (node (ref "U3") (pin "5") (pinfunction "VIN_5") (pintype "passive"))
    )
    (net (code "60") (name "GND") (class "Default")
      (node (ref "C1") (pin "1") (pinfunction "1_1") (pintype "passive"))
      (node (ref "C10") (pin "2") (pinfunction "2_2") (pintype "passive"))
      (node (ref "C11") (pin "2") (pinfunction "2_2") (pintype "passive"))
      (node (ref "C12") (pin "1") (pinfunction "1_1") (pintype "passive"))
      (node (ref "C13") (pin "1") (pinfunction "1_1") (pintype "passive"))
      (node (ref "C14") (pin "1") (pinfunction "1_1") (pintype "passive"))
      (node (ref "C15") (pin "1") (pinfunction "1_1") (pintype "passive"))
      (node (ref "C16") (pin "2") (pinfunction "2_2") (pintype "passive"))
      (node (ref "C17") (pin "1") (pinfunction "1_1") (pintype "passive"))
      (node (ref "C18") (pin "2") (pinfunction "2_2") (pintype "passive"))
      (node (ref "C19") (pin "2") (pinfunction "2_2") (pintype "passive"))
      (node (ref "C2") (pin "2") (pinfunction "2_2") (pintype "passive"))
      (node (ref "C20") (pin "2") (pinfunction "2_2") (pintype "passive"))
      (node (ref "C21") (pin "2") (pinfunction "2_2") (pintype "passive"))
      (node (ref "C22") (pin "2") (pinfunction "2_2") (pintype "passive"))
      (node (ref "C23") (pin "2") (pinfunction "2_2") (pintype "passive"))
      (node (ref "C24") (pin "2") (pinfunction "2_2") (pintype "passive"))
      (node (ref "C25") (pin "2") (pinfunction "2_2") (pintype "passive"))
      (node (ref "C26") (pin "1") (pinfunction "1_1") (pintype "passive"))
      (node (ref "C27") (pin "1") (pinfunction "1_1") (pintype "passive"))
      (node (ref "C28") (pin "1") (pinfunction "1_1") (pintype "passive"))
      (node (ref "C29") (pin "1") (pinfunction "1_1") (pintype "passive"))
      (node (ref "C3") (pin "1") (pinfunction "1_1") (pintype "passive"))
      (node (ref "C30") (pin "1") (pinfunction "1_1") (pintype "passive"))
      (node (ref "C31") (pin "1") (pinfunction "1_1") (pintype "passive"))
      (node (ref "C32") (pin "1") (pinfunction "1_1") (pintype "passive"))
      (node (ref "C33") (pin "1") (pinfunction "1_1") (pintype "passive"))
      (node (ref "C4") (pin "2") (pinfunction "2_2") (pintype "passive"))
      (node (ref "C5") (pin "2") (pinfunction "2_2") (pintype "passive"))
      (node (ref "C7") (pin "2") (pinfunction "2_2") (pintype "passive"))
      (node (ref "C8") (pin "1") (pinfunction "1_1") (pintype "passive"))
      (node (ref "DEBUG") (pin "0") (pinfunction "0_0") (pintype "passive"))
      (node (ref "DEBUG") (pin "4") (pinfunction "4_4") (pintype "passive"))
      (node (ref "E1") (pin "2") (pinfunction "K_2") (pintype "passive"))
      (node (ref "GND1") (pin "1") (pinfunction "1_1") (pintype "passive"))
      (node (ref "GND2") (pin "1") (pinfunction "1_1") (pintype "passive"))
      (node (ref "H1") (pin "1") (pinfunction "1_1") (pintype "passive"))
      (node (ref "H2") (pin "1") (pinfunction "1_1") (pintype "passive"))
      (node (ref "H3") (pin "1") (pinfunction "1_1") (pintype "passive"))
      (node (ref "H4") (pin "1") (pinfunction "1_1") (pintype "passive"))
      (node (ref "LED2") (pin "2") (pinfunction "K_2") (pintype "passive"))
      (node (ref "LED3") (pin "2") (pinfunction "K_2") (pintype "passive"))
      (node (ref "LED4") (pin "2") (pinfunction "K_2") (pintype "passive"))
      (node (ref "Q1") (pin "2") (pinfunction "E_2") (pintype "passive"))
      (node (ref "Q2") (pin "2") (pinfunction "E_2") (pintype "passive"))
      (node (ref "Q3") (pin "2") (pinfunction "S_2") (pintype "passive"))
      (node (ref "R11") (pin "2") (pinfunction "2_2") (pintype "passive"))
      (node (ref "R12") (pin "1") (pinfunction "1_1") (pintype "passive"))
      (node (ref "R13") (pin "2") (pinfunction "2_2") (pintype "passive"))
      (node (ref "R17") (pin "2") (pinfunction "2_2") (pintype "passive"))
      (node (ref "R2") (pin "2") (pinfunction "2_2") (pintype "passive"))
      (node (ref "R31") (pin "1") (pinfunction "1_1") (pintype "passive"))
      (node (ref "R4") (pin "2") (pinfunction "2_2") (pintype "passive"))
      (node (ref "R7") (pin "2") (pinfunction "2_2") (pintype "passive"))
      (node (ref "R9") (pin "2") (pinfunction "2_2") (pintype "passive"))
      (node (ref "REST1") (pin "2") (pinfunction "2_2") (pintype "passive"))
      (node (ref "SBUS") (pin "1") (pinfunction "1_1") (pintype "passive"))
      (node (ref "U1") (pin "12") (pinfunction "VSSA_12") (pintype "power_in"))
      (node (ref "U1") (pin "18") (pinfunction "VSS_18") (pintype "power_in"))
      (node (ref "U1") (pin "63") (pinfunction "VSS_63") (pintype "power_in"))
      (node (ref "U2") (pin "4") (pinfunction "GND_4") (pintype "passive"))
      (node (ref "U3") (pin "3") (pinfunction "GND_3") (pintype "passive"))
      (node (ref "U3") (pin "4") (pinfunction "GND_4") (pintype "passive"))
      (node (ref "U4") (pin "1") (pinfunction "GND_1") (pintype "passive"))
      (node (ref "U5") (pin "11") (pinfunction "GND_11") (pintype "passive"))
      (node (ref "U5") (pin "9") (pinfunction "GND_9") (pintype "passive"))
      (node (ref "U6") (pin "10") (pinfunction "RESV_10") (pintype "passive"))
      (node (ref "U6") (pin "11") (pinfunction "RESV_11") (pintype "passive"))
      (node (ref "U6") (pin "12") (pinfunction "RESV_12") (pintype "passive"))
      (node (ref "U6") (pin "13") (pinfunction "GND_13") (pintype "passive"))
      (node (ref "U6") (pin "15") (pinfunction "RESV_15") (pintype "passive"))
      (node (ref "U6") (pin "8") (pinfunction "FSYNC_8") (pintype "passive"))
      (node (ref "U6") (pin "9") (pinfunction "RESV_9") (pintype "passive"))
      (node (ref "U7") (pin "1") (pinfunction "GND_1") (pintype "passive"))
      (node (ref "U7") (pin "7") (pinfunction "GND_7") (pintype "passive"))
      (node (ref "U8") (pin "2") (pinfunction "GND_2") (pintype "power_in"))
      (node (ref "U8") (pin "5") (pinfunction "SHDN_5") (pintype "input"))
      (node (ref "U8") (pin "8") (pinfunction "RS_8") (pintype "input"))
      (node (ref "U9") (pin "2") (pinfunction "GND_2") (pintype "power_in"))
      (node (ref "U9") (pin "5") (pinfunction "SHDN_5") (pintype "input"))
      (node (ref "U9") (pin "8") (pinfunction "RS_8") (pintype "input"))
      (node (ref "USB1") (pin "0") (pinfunction "0_0") (pintype "passive"))
      (node (ref "USB1") (pin "A1") (pinfunction "GND_A1") (pintype "passive"))
      (node (ref "USB1") (pin "A12") (pinfunction "GND_A12") (pintype "passive"))
      (node (ref "USB1") (pin "B1") (pinfunction "GND_B1") (pintype "passive"))
      (node (ref "USB1") (pin "B12") (pinfunction "GND_B12") (pintype "passive"))
      (node (ref "X1") (pin "2") (pinfunction "2_2") (pintype "passive"))
      (node (ref "X1") (pin "4") (pinfunction "4_4") (pintype "passive"))
    )
    (net (code "61") (name "Net-(BBE1-Pad2)") (class "Default")
      (node (ref "BBE1") (pin "2") (pinfunction "2_2") (pintype "passive"))
      (node (ref "R23") (pin "2") (pinfunction "2_2") (pintype "passive"))
    )
    (net (code "62") (name "Net-(LED1-K)") (class "Default")
      (node (ref "LED1") (pin "2") (pinfunction "K_2") (pintype "passive"))
      (node (ref "R13") (pin "1") (pinfunction "1_1") (pintype "passive"))
    )
    (net (code "63") (name "Net-(LED2-A)") (class "Default")
      (node (ref "LED2") (pin "1") (pinfunction "A_1") (pintype "passive"))
      (node (ref "R14") (pin "1") (pinfunction "1_1") (pintype "passive"))
    )
    (net (code "64") (name "Net-(LED3-A)") (class "Default")
      (node (ref "LED3") (pin "1") (pinfunction "A_1") (pintype "passive"))
      (node (ref "R15") (pin "1") (pinfunction "1_1") (pintype "passive"))
    )
    (net (code "65") (name "Net-(LED4-A)") (class "Default")
      (node (ref "LED4") (pin "1") (pinfunction "A_1") (pintype "passive"))
      (node (ref "R18") (pin "1") (pinfunction "1_1") (pintype "passive"))
    )
    (net (code "66") (name "Net-(Q1-B)") (class "Default")
      (node (ref "Q1") (pin "1") (pinfunction "B_1") (pintype "passive"))
      (node (ref "R5") (pin "2") (pinfunction "2_2") (pintype "passive"))
    )
    (net (code "67") (name "Net-(Q2-B)") (class "Default")
      (node (ref "Q2") (pin "1") (pinfunction "B_1") (pintype "passive"))
      (node (ref "R25") (pin "2") (pinfunction "2_2") (pintype "passive"))
    )
    (net (code "68") (name "Net-(Q2-C)") (class "Default")
      (node (ref "BBE1") (pin "1") (pinfunction "1_1") (pintype "passive"))
      (node (ref "Q2") (pin "3") (pinfunction "C_3") (pintype "passive"))
    )
    (net (code "69") (name "Net-(Q3-D)") (class "Default")
      (node (ref "Q3") (pin "3") (pinfunction "D_3") (pintype "passive"))
      (node (ref "R32") (pin "2") (pinfunction "2_2") (pintype "passive"))
      (node (ref "R33") (pin "2") (pinfunction "2_2") (pintype "passive"))
    )
    (net (code "70") (name "Net-(Q3-G)") (class "Default")
      (node (ref "Q3") (pin "1") (pinfunction "G_1") (pintype "passive"))
      (node (ref "R30") (pin "2") (pinfunction "2_2") (pintype "passive"))
      (node (ref "R31") (pin "2") (pinfunction "2_2") (pintype "passive"))
    )
    (net (code "71") (name "Net-(R5-Pad1)") (class "Default")
      (node (ref "R5") (pin "1") (pinfunction "1_1") (pintype "passive"))
      (node (ref "SBUS") (pin "3") (pinfunction "3_3") (pintype "passive"))
    )
    (net (code "72") (name "Net-(U1-PB2{slash}BOOT1)") (class "Default")
      (node (ref "R12") (pin "2") (pinfunction "2_2") (pintype "passive"))
      (node (ref "U1") (pin "28") (pinfunction "PB2/BOOT1_28") (pintype "bidirectional"))
    )
    (net (code "73") (name "Net-(U1-PH0{slash}OSC_IN)") (class "Default")
      (node (ref "C1") (pin "2") (pinfunction "2_2") (pintype "passive"))
      (node (ref "U1") (pin "5") (pinfunction "PH0/OSC_IN_5") (pintype "input"))
      (node (ref "X1") (pin "1") (pinfunction "1_1") (pintype "passive"))
    )
    (net (code "74") (name "Net-(U1-PH1{slash}OS_OUT)") (class "Default")
      (node (ref "C3") (pin "2") (pinfunction "2_2") (pintype "passive"))
      (node (ref "U1") (pin "6") (pinfunction "PH1/OS_OUT_6") (pintype "input"))
      (node (ref "X1") (pin "3") (pinfunction "3_3") (pintype "passive"))
    )
    (net (code "75") (name "Net-(U1-VCAP_1)") (class "Default")
      (node (ref "C14") (pin "2") (pinfunction "2_2") (pintype "passive"))
      (node (ref "U1") (pin "31") (pinfunction "VCAP_1_31") (pintype "passive"))
    )
    (net (code "76") (name "Net-(U1-VCAP_2)") (class "Default")
      (node (ref "C7") (pin "1") (pinfunction "1_1") (pintype "passive"))
      (node (ref "U1") (pin "47") (pinfunction "VCAP_2_47") (pintype "passive"))
    )
    (net (code "77") (name "Net-(U1-VDDA)") (class "Default")
      (node (ref "C4") (pin "1") (pinfunction "1_1") (pintype "passive"))
      (node (ref "C5") (pin "1") (pinfunction "1_1") (pintype "passive"))
      (node (ref "L1") (pin "2") (pinfunction "2_2") (pintype "passive"))
      (node (ref "U1") (pin "13") (pinfunction "VDDA_13") (pintype "power_in"))
    )
    (net (code "78") (name "Net-(U3-BS)") (class "Default")
      (node (ref "C9") (pin "2") (pinfunction "2_2") (pintype "passive"))
      (node (ref "U3") (pin "7") (pinfunction "BS_7") (pintype "passive"))
    )
    (net (code "79") (name "Net-(U3-EN)") (class "Default")
      (node (ref "R7") (pin "1") (pinfunction "1_1") (pintype "passive"))
      (node (ref "R8") (pin "2") (pinfunction "2_2") (pintype "passive"))
      (node (ref "U3") (pin "8") (pinfunction "EN_8") (pintype "passive"))
    )
    (net (code "80") (name "Net-(U3-FB)") (class "Default")
      (node (ref "C6") (pin "2") (pinfunction "2_2") (pintype "passive"))
      (node (ref "R10") (pin "2") (pinfunction "2_2") (pintype "passive"))
      (node (ref "R9") (pin "1") (pinfunction "1_1") (pintype "passive"))
      (node (ref "U3") (pin "1") (pinfunction "FB_1") (pintype "passive"))
    )
    (net (code "81") (name "Net-(U3-FS)") (class "Default")
      (node (ref "R11") (pin "1") (pinfunction "1_1") (pintype "passive"))
      (node (ref "U3") (pin "2") (pinfunction "FS_2") (pintype "passive"))
    )
    (net (code "82") (name "Net-(U3-LX)") (class "Default")
      (node (ref "C9") (pin "1") (pinfunction "1_1") (pintype "passive"))
      (node (ref "L2") (pin "1") (pinfunction "1_1") (pintype "passive"))
      (node (ref "U3") (pin "6") (pinfunction "LX_6") (pintype "passive"))
    )
    (net (code "83") (name "Net-(U5-C1)") (class "Default")
      (node (ref "C33") (pin "2") (pinfunction "2_2") (pintype "passive"))
      (node (ref "U5") (pin "10") (pinfunction "C1_10") (pintype "passive"))
    )
    (net (code "84") (name "Net-(U6-REGOUT)") (class "Default")
      (node (ref "C25") (pin "1") (pinfunction "1_1") (pintype "passive"))
      (node (ref "U6") (pin "14") (pinfunction "REGOUT_14") (pintype "passive"))
    )
    (net (code "85") (name "VUSB") (class "Default")
      (node (ref "D1") (pin "1") (pinfunction "A_1") (pintype "passive"))
      (node (ref "R24") (pin "2") (pinfunction "2_2") (pintype "passive"))
      (node (ref "USB1") (pin "A4") (pinfunction "VBUS_A4") (pintype "passive"))
      (node (ref "USB1") (pin "A9") (pinfunction "VBUS_A9") (pintype "passive"))
      (node (ref "USB1") (pin "B4") (pinfunction "VBUS_B4") (pintype "passive"))
      (node (ref "USB1") (pin "B9") (pinfunction "VBUS_B9") (pintype "passive"))
    )
    (net (code "86") (name "unconnected-(U5-CAD0-Pad5)") (class "Default")
      (node (ref "U5") (pin "5") (pinfunction "CAD0_5") (pintype "passive+no_connect"))
    )
    (net (code "87") (name "unconnected-(U5-CAD1-Pad6)") (class "Default")
      (node (ref "U5") (pin "6") (pinfunction "CAD1_6") (pintype "passive+no_connect"))
    )
    (net (code "88") (name "unconnected-(U5-NC-Pad3)") (class "Default")
      (node (ref "U5") (pin "3") (pinfunction "NC_3") (pintype "passive+no_connect"))
    )
    (net (code "89") (name "unconnected-(U5-NC-Pad4)") (class "Default")
      (node (ref "U5") (pin "4") (pinfunction "NC_4") (pintype "passive+no_connect"))
    )
    (net (code "90") (name "unconnected-(U5-NC-Pad8)") (class "Default")
      (node (ref "U5") (pin "8") (pinfunction "NC_8") (pintype "passive+no_connect"))
    )
    (net (code "91") (name "unconnected-(U5-NC-Pad12)") (class "Default")
      (node (ref "U5") (pin "12") (pinfunction "NC_12") (pintype "passive+no_connect"))
    )
    (net (code "92") (name "unconnected-(U5-VPP-Pad7)") (class "Default")
      (node (ref "U5") (pin "7") (pinfunction "VPP_7") (pintype "passive+no_connect"))
    )
    (net (code "93") (name "unconnected-(U6-RESV-Pad7)") (class "Default")
      (node (ref "U6") (pin "7") (pinfunction "RESV_7") (pintype "passive+no_connect"))
    )
    (net (code "94") (name "unconnected-(U7-CSB-Pad2)") (class "Default")
      (node (ref "U7") (pin "2") (pinfunction "CSB_2") (pintype "passive+no_connect"))
    )
    (net (code "95") (name "unconnected-(U7-SDO-Pad5)") (class "Default")
      (node (ref "U7") (pin "5") (pinfunction "SDO_5") (pintype "passive+no_connect"))
    )
    (net (code "96") (name "unconnected-(USB1-CC1-PadA5)") (class "Default")
      (node (ref "USB1") (pin "A5") (pinfunction "CC1_A5") (pintype "passive+no_connect"))
    )
    (net (code "97") (name "unconnected-(USB1-CC2-PadB5)") (class "Default")
      (node (ref "USB1") (pin "B5") (pinfunction "CC2_B5") (pintype "passive+no_connect"))
    )
    (net (code "98") (name "unconnected-(USB1-SBU2-PadB8)") (class "Default")
      (node (ref "USB1") (pin "B8") (pinfunction "SBU2_B8") (pintype "passive+no_connect"))
    )
    (net (code "99") (name "unconnected-(USB1-SUB1-PadA8)") (class "Default")
      (node (ref "USB1") (pin "A8") (pinfunction "SUB1_A8") (pintype "passive+no_connect"))
    )
  )
)
